# LB-word-PSU-3V.net
KiCad netlist of a schematic drawn in Altium Designer
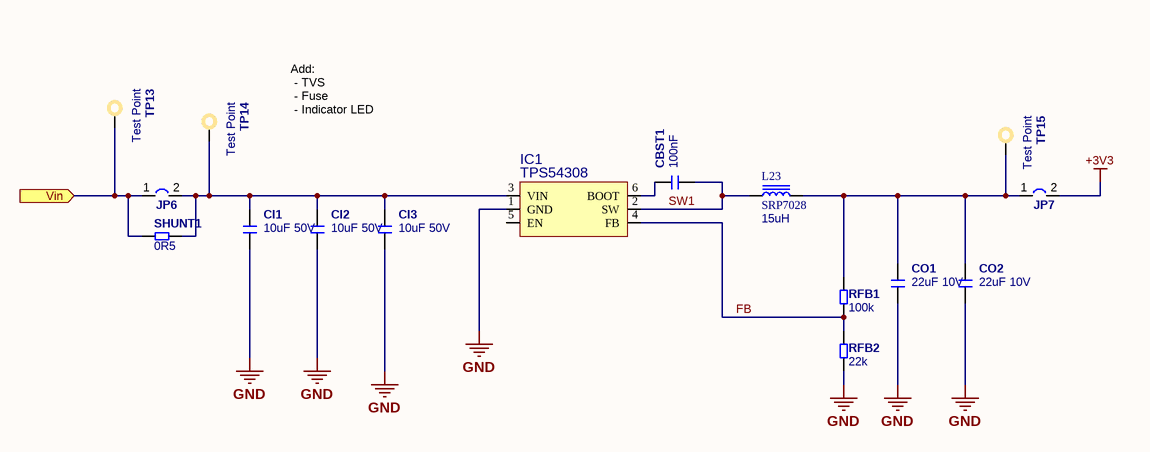
[diagram p0: LB-word-PSU-3V.SchDoc]

(export (version "E")
  (design (tool "Eeschema 10.0.6"))
  (components
    (comp (ref "CBST1")
      (value "100nF")
      (footprint "C0603_N")
      (description "Capacitor MLCC")
      (fields
        (field (name "MANUFACTURER") "Yageo")
        (field (name "MANUFACTURER PART NUMBER") "CC0603KRX7R9BB104")
      )
      (libsource (lib "wes") (part "Capacitor"))
    )
    (comp (ref "CI1")
      (value "10uF 50V")
      (footprint "C1210_N")
      (description "Capacitor MLCC")
      (fields
        (field (name "MANUFACTURER") "Yageo")
        (field (name "MANUFACTURER PART NUMBER") "CC0603KRX7R9BB104")
      )
      (libsource (lib "wes") (part "Capacitor"))
    )
    (comp (ref "CI2")
      (value "10uF 50V")
      (footprint "C1210_N")
      (description "Capacitor MLCC")
      (fields
        (field (name "MANUFACTURER") "Yageo")
        (field (name "MANUFACTURER PART NUMBER") "CC0603KRX7R9BB104")
      )
      (libsource (lib "wes") (part "Capacitor"))
    )
    (comp (ref "CI3")
      (value "10uF 50V")
      (footprint "C1210_N")
      (description "Capacitor MLCC")
      (fields
        (field (name "MANUFACTURER") "Yageo")
        (field (name "MANUFACTURER PART NUMBER") "CC0603KRX7R9BB104")
      )
      (libsource (lib "wes") (part "Capacitor"))
    )
    (comp (ref "CO1")
      (value "22uF 10V")
      (footprint "C1210_N")
      (description "Capacitor MLCC")
      (fields
        (field (name "MANUFACTURER") "Yageo")
        (field (name "MANUFACTURER PART NUMBER") "CC0603KRX7R9BB104")
      )
      (libsource (lib "wes") (part "Capacitor"))
    )
    (comp (ref "CO2")
      (value "22uF 10V")
      (footprint "C1210_N")
      (description "Capacitor MLCC")
      (fields
        (field (name "MANUFACTURER") "Yageo")
        (field (name "MANUFACTURER PART NUMBER") "CC0603KRX7R9BB104")
      )
      (libsource (lib "wes") (part "Capacitor"))
    )
    (comp (ref "IC1")
      (value "TPS54308")
      (footprint "SOT23")
      (description "Buck Converter")
      (libsource (lib "wes") (part "TPS54308"))
    )
    (comp (ref "JP6")
      (value "Jumper 2W")
      (footprint "Jumper SMD 2W NO")
      (libsource (lib "wes") (part "Jumper 2W"))
    )
    (comp (ref "JP7")
      (value "Jumper 2W")
      (footprint "Jumper SMD 2W NO")
      (libsource (lib "wes") (part "Jumper 2W"))
    )
    (comp (ref "L23")
      (value "SRP7028")
      (footprint "Inductor SRP7028")
      (fields (field (name "ALTIUM_VALUE") "15uH"))
      (libsource (lib "wes") (part "Inductor"))
    )
    (comp (ref "RFB1")
      (value "100k")
      (footprint "R0603")
      (fields (field (name "PUBLISHER") "Altium Limited"))
      (libsource (lib "wes") (part "Resistor"))
    )
    (comp (ref "RFB2")
      (value "22k")
      (footprint "R0603")
      (fields (field (name "PUBLISHER") "Altium Limited"))
      (libsource (lib "wes") (part "Resistor"))
    )
    (comp (ref "SHUNT1")
      (value "0R5")
      (footprint "R0603")
      (fields (field (name "PUBLISHER") "Altium Limited"))
      (libsource (lib "wes") (part "Resistor"))
    )
    (comp (ref "TP13")
      (value "Test Point")
      (footprint "TestPoint-1.2mm")
      (libsource (lib "wes") (part "Test Point"))
    )
    (comp (ref "TP14")
      (value "Test Point")
      (footprint "TestPoint-1.2mm")
      (libsource (lib "wes") (part "Test Point"))
    )
    (comp (ref "TP15")
      (value "Test Point")
      (footprint "TestPoint-1.2mm")
      (libsource (lib "wes") (part "Test Point"))
    )
  )
  (nets
    (net (code "1") (name "+3V3") (class "Default")
      (node (ref "JP7") (pin "2") (pinfunction "2_2") (pintype "passive"))
    )
    (net (code "2") (name "/FB") (class "Default")
      (node (ref "IC1") (pin "4") (pinfunction "FB_4") (pintype "passive"))
      (node (ref "RFB1") (pin "1") (pinfunction "1_1") (pintype "passive"))
      (node (ref "RFB2") (pin "2") (pinfunction "2_2") (pintype "passive"))
    )
    (net (code "3") (name "/SW1") (class "Default")
      (node (ref "CBST1") (pin "2") (pintype "passive"))
      (node (ref "IC1") (pin "2") (pinfunction "SW_2") (pintype "passive"))
      (node (ref "L23") (pin "1") (pinfunction "1_1") (pintype "passive"))
    )
    (net (code "4") (name "/Vin") (class "Default")
      (node (ref "JP6") (pin "1") (pinfunction "1_1") (pintype "passive"))
      (node (ref "SHUNT1") (pin "1") (pinfunction "1_1") (pintype "passive"))
      (node (ref "TP13") (pin "1") (pinfunction "1_1") (pintype "passive"))
    )
    (net (code "5") (name "GND") (class "Default")
      (node (ref "CI1") (pin "2") (pintype "passive"))
      (node (ref "CI2") (pin "2") (pintype "passive"))
      (node (ref "CI3") (pin "2") (pintype "passive"))
      (node (ref "CO1") (pin "2") (pintype "passive"))
      (node (ref "CO2") (pin "2") (pintype "passive"))
      (node (ref "IC1") (pin "1") (pinfunction "GND_1") (pintype "passive"))
      (node (ref "RFB2") (pin "1") (pinfunction "1_1") (pintype "passive"))
    )
    (net (code "6") (name "Net-(CO1-Pad1)") (class "Default")
      (node (ref "CO1") (pin "1") (pintype "passive"))
      (node (ref "CO2") (pin "1") (pintype "passive"))
      (node (ref "JP7") (pin "1") (pinfunction "1_1") (pintype "passive"))
      (node (ref "L23") (pin "2") (pinfunction "2_2") (pintype "passive"))
      (node (ref "RFB1") (pin "2") (pinfunction "2_2") (pintype "passive"))
      (node (ref "TP15") (pin "1") (pinfunction "1_1") (pintype "passive"))
    )
    (net (code "7") (name "Net-(IC1-BOOT)") (class "Default")
      (node (ref "CBST1") (pin "1") (pintype "passive"))
      (node (ref "IC1") (pin "6") (pinfunction "BOOT_6") (pintype "passive"))
    )
    (net (code "8") (name "Net-(IC1-VIN)") (class "Default")
      (node (ref "CI1") (pin "1") (pintype "passive"))
      (node (ref "CI2") (pin "1") (pintype "passive"))
      (node (ref "CI3") (pin "1") (pintype "passive"))
      (node (ref "IC1") (pin "3") (pinfunction "VIN_3") (pintype "passive"))
      (node (ref "JP6") (pin "2") (pinfunction "2_2") (pintype "passive"))
      (node (ref "SHUNT1") (pin "2") (pinfunction "2_2") (pintype "passive"))
      (node (ref "TP14") (pin "1") (pinfunction "1_1") (pintype "passive"))
    )
    (net (code "9") (name "unconnected-(IC1-EN-Pad5)") (class "Default")
      (node (ref "IC1") (pin "5") (pinfunction "EN_5") (pintype "passive"))
    )
  )
)
